# MCU.net
KiCad netlist of a schematic drawn in Altium Designer
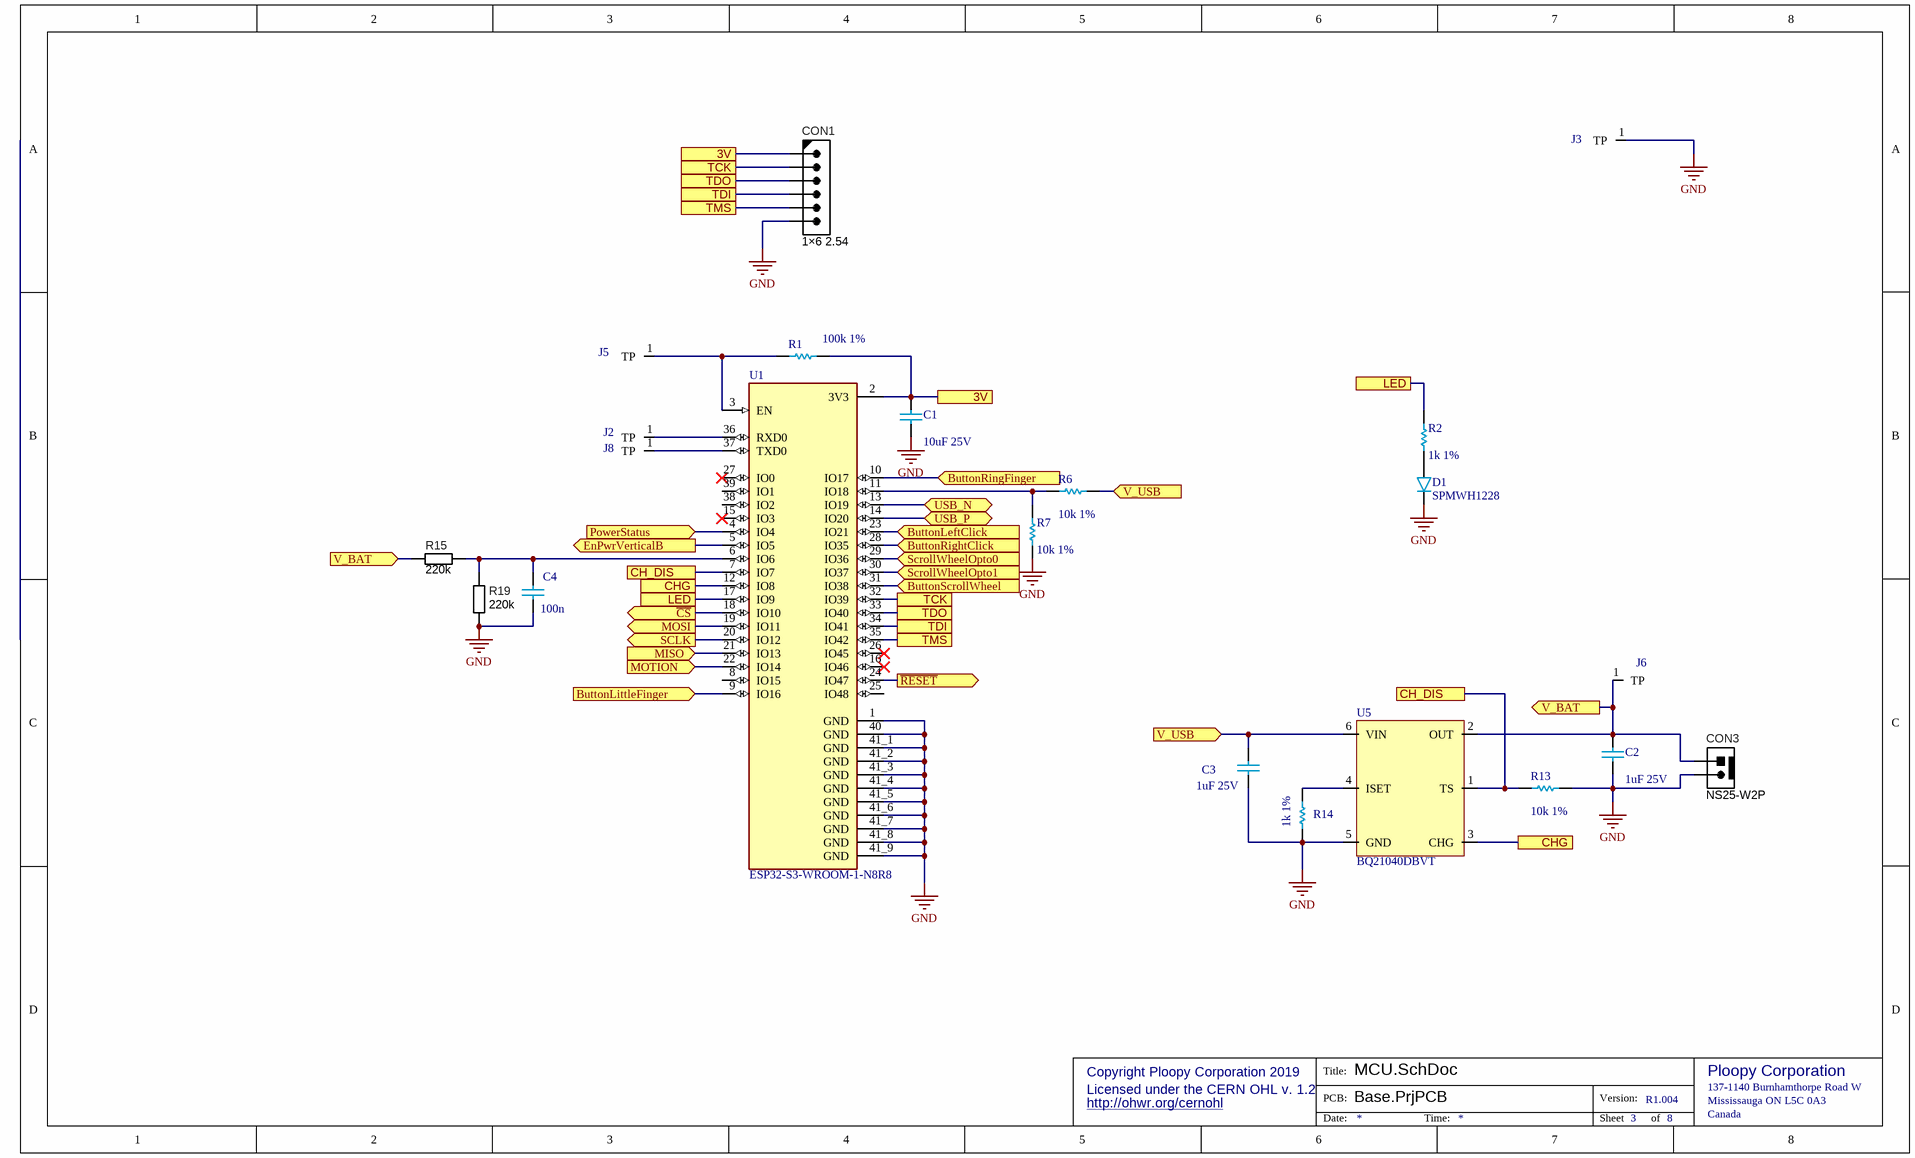
[diagram p0: MCU.SchDoc]

(export (version "E")
  (design (tool "Eeschema 10.0.6"))
  (components
    (comp (ref "C1")
      (value "10uF 25V")
      (footprint "C0603")
      (description "0805, X5R or better")
      (fields (field (name "Comment") "0805"))
      (libsource (lib "Chip_Passives") (part "Cap 10uF 25V"))
    )
    (comp (ref "C2")
      (value "1uF 25V")
      (footprint "C0603")
      (description "0805, X5R or better")
      (fields (field (name "Comment") "0805"))
      (libsource (lib "Chip_Passives") (part "Cap 1uF 25V"))
    )
    (comp (ref "C3")
      (value "1uF 25V")
      (footprint "C0603")
      (description "0805, X5R or better")
      (fields (field (name "Comment") "0805"))
      (libsource (lib "Chip_Passives") (part "Cap 1uF 25V"))
    )
    (comp (ref "C4")
      (value "100n")
      (footprint "C0603")
      (description "0805, X5R or better")
      (fields (field (name "Comment") "0805"))
      (libsource (lib "Chip_Passives") (part "Cap 1uF 25V"))
    )
    (comp (ref "CON1")
      (value "1×6 2.54")
      (footprint "THT_CON:PH2.54_1X6")
      (description "1x3 standart 100mil pinheader")
      (libsource (lib "Connectors") (part "PH2.54_1X6"))
    )
    (comp (ref "CON3")
      (value "NS25-W2P")
      (footprint "THT_CON:MOLEST_L2.54_2W")
      (description "Molex-like 2.54mm connector with lock")
      (libsource (lib "Connectors") (part "MOLEST_L2.54_2W"))
    )
    (comp (ref "D1")
      (value "SPMWH1228")
      (footprint "SPMWH1228")
      (description "3V/0.5W white LED, 2.8mm x 3.5mm")
      (libsource (lib "LEDs") (part "SPMWH1228"))
    )
    (comp (ref "J2")
      (value "TestPoint")
      (footprint "TestPoint")
      (libsource (lib "Schlib1") (part "TestPoint"))
    )
    (comp (ref "J3")
      (value "TestPoint")
      (footprint "TestPoint")
      (libsource (lib "Schlib1") (part "TestPoint"))
    )
    (comp (ref "J5")
      (value "TestPoint")
      (footprint "TestPoint")
      (libsource (lib "Schlib1") (part "TestPoint"))
    )
    (comp (ref "J6")
      (value "TestPoint")
      (footprint "TestPoint")
      (libsource (lib "Schlib1") (part "TestPoint"))
    )
    (comp (ref "J8")
      (value "TestPoint")
      (footprint "TestPoint")
      (libsource (lib "Schlib1") (part "TestPoint"))
    )
    (comp (ref "R1")
      (value "100k 1%")
      (footprint "R0603")
      (description "Chip resistor")
      (fields (field (name "Comment") "0805"))
      (libsource (lib "Chip_Passives") (part "Res 100k 1% 0805"))
    )
    (comp (ref "R2")
      (value "1k 1%")
      (footprint "R0603")
      (description "Chip resistor, 1/8W 100PPM")
      (fields (field (name "Comment") "0805"))
      (libsource (lib "Chip_Passives") (part "Res 1k 1% 0805"))
    )
    (comp (ref "R6")
      (value "10k 1%")
      (footprint "R0603")
      (description "Chip resistor")
      (fields (field (name "Comment") "0805"))
      (libsource (lib "Chip_Passives") (part "Res 10k 1% 0805"))
    )
    (comp (ref "R7")
      (value "10k 1%")
      (footprint "R0603")
      (description "Chip resistor")
      (fields (field (name "Comment") "0805"))
      (libsource (lib "Chip_Passives") (part "Res 10k 1% 0805"))
    )
    (comp (ref "R13")
      (value "10k 1%")
      (footprint "R0603")
      (description "Chip resistor")
      (fields (field (name "Comment") "0805"))
      (libsource (lib "Chip_Passives") (part "Res 10k 1% 0805"))
    )
    (comp (ref "R14")
      (value "1k 1%")
      (footprint "R0603")
      (description "Chip resistor, 1/8W 100PPM")
      (fields (field (name "Comment") "0805"))
      (libsource (lib "Chip_Passives") (part "Res 1k 1% 0805"))
    )
    (comp (ref "R15")
      (value "220k")
      (footprint "SMD_PASSIVES:R0603")
      (description "Generic 0603 resistor footprint")
      (libsource (lib "") (part "R0603_1"))
    )
    (comp (ref "R19")
      (value "220k")
      (footprint "SMD_PASSIVES:R0603")
      (description "Generic 0603 resistor footprint")
      (libsource (lib "Passives") (part "R0603"))
    )
    (comp (ref "U1")
      (value "ESP32-S3-WROOM-1-N8R8")
      (footprint "XCVR_ESP32S3WROOM1N8R8")
      (description "Bluetooth, WiFi 802.11b/g/n, Bluetooth v5.0 Transceiver Module 2.4GHz PCB Trace Surface Mount")
      (fields (field (name "MF") "Espressif Systems"))
      (libsource (lib "ESP32-S3-WROOM-1-N8R8") (part "ESP32-S3-WROOM-1-N8R8"))
    )
    (comp (ref "U5")
      (value "BQ21040DBVT")
      (footprint "PESD3V3S4UD - SOT95P275X110-6N")
      (libsource (lib "Schlib1") (part "BQ21040DBVT"))
    )
  )
  (nets
    (net (code "1") (name "/3V") (class "Default")
      (node (ref "C1") (pin "2") (pinfunction "2_2") (pintype "passive"))
      (node (ref "CON1") (pin "1") (pinfunction "1_1") (pintype "passive"))
      (node (ref "R1") (pin "2") (pinfunction "2_2") (pintype "passive"))
      (node (ref "U1") (pin "2") (pinfunction "3V3_2") (pintype "power_in"))
    )
    (net (code "2") (name "/ButtonLeftClick") (class "Default")
      (node (ref "U1") (pin "23") (pinfunction "IO21_23") (pintype "bidirectional"))
    )
    (net (code "3") (name "/ButtonLittleFinger") (class "Default")
      (node (ref "U1") (pin "9") (pinfunction "IO16_9") (pintype "bidirectional"))
    )
    (net (code "4") (name "/ButtonRightClick") (class "Default")
      (node (ref "U1") (pin "28") (pinfunction "IO35_28") (pintype "bidirectional"))
    )
    (net (code "5") (name "/ButtonRingFinger") (class "Default")
      (node (ref "U1") (pin "10") (pinfunction "IO17_10") (pintype "bidirectional"))
    )
    (net (code "6") (name "/ButtonScrollWheel") (class "Default")
      (node (ref "U1") (pin "31") (pinfunction "IO38_31") (pintype "bidirectional"))
    )
    (net (code "7") (name "/CHG") (class "Default")
      (node (ref "U1") (pin "12") (pinfunction "IO8_12") (pintype "bidirectional"))
      (node (ref "U5") (pin "3") (pinfunction "CHG_3") (pintype "passive"))
    )
    (net (code "8") (name "/CH_DIS") (class "Default")
      (node (ref "R13") (pin "2") (pinfunction "2_2") (pintype "passive"))
      (node (ref "U1") (pin "7") (pinfunction "IO7_7") (pintype "bidirectional"))
      (node (ref "U5") (pin "1") (pinfunction "TS_1") (pintype "passive"))
    )
    (net (code "9") (name "/EnPwrVerticalB") (class "Default")
      (node (ref "U1") (pin "5") (pinfunction "IO5_5") (pintype "bidirectional"))
    )
    (net (code "10") (name "/LED") (class "Default")
      (node (ref "R2") (pin "2") (pinfunction "2_2") (pintype "passive"))
      (node (ref "U1") (pin "17") (pinfunction "IO9_17") (pintype "bidirectional"))
    )
    (net (code "11") (name "/MISO") (class "Default")
      (node (ref "U1") (pin "21") (pinfunction "IO13_21") (pintype "bidirectional"))
    )
    (net (code "12") (name "/MOSI") (class "Default")
      (node (ref "U1") (pin "19") (pinfunction "IO11_19") (pintype "bidirectional"))
    )
    (net (code "13") (name "/MOTION") (class "Default")
      (node (ref "U1") (pin "22") (pinfunction "IO14_22") (pintype "bidirectional"))
    )
    (net (code "14") (name "/PowerStatus") (class "Default")
      (node (ref "U1") (pin "4") (pinfunction "IO4_4") (pintype "bidirectional"))
    )
    (net (code "15") (name "/SCLK") (class "Default")
      (node (ref "U1") (pin "20") (pinfunction "IO12_20") (pintype "bidirectional"))
    )
    (net (code "16") (name "/ScrollWheelOpto0") (class "Default")
      (node (ref "U1") (pin "29") (pinfunction "IO36_29") (pintype "bidirectional"))
    )
    (net (code "17") (name "/ScrollWheelOpto1") (class "Default")
      (node (ref "U1") (pin "30") (pinfunction "IO37_30") (pintype "bidirectional"))
    )
    (net (code "18") (name "/TCK") (class "Default")
      (node (ref "CON1") (pin "2") (pinfunction "2_2") (pintype "passive"))
      (node (ref "U1") (pin "32") (pinfunction "IO39_32") (pintype "bidirectional"))
    )
    (net (code "19") (name "/TDI") (class "Default")
      (node (ref "CON1") (pin "4") (pinfunction "4_4") (pintype "passive"))
      (node (ref "U1") (pin "34") (pinfunction "IO41_34") (pintype "bidirectional"))
    )
    (net (code "20") (name "/TDO") (class "Default")
      (node (ref "CON1") (pin "3") (pinfunction "3_3") (pintype "passive"))
      (node (ref "U1") (pin "33") (pinfunction "IO40_33") (pintype "bidirectional"))
    )
    (net (code "21") (name "/TMS") (class "Default")
      (node (ref "CON1") (pin "5") (pinfunction "5_5") (pintype "passive"))
      (node (ref "U1") (pin "35") (pinfunction "IO42_35") (pintype "bidirectional"))
    )
    (net (code "22") (name "/USB_N") (class "Default")
      (node (ref "U1") (pin "13") (pinfunction "IO19_13") (pintype "bidirectional"))
    )
    (net (code "23") (name "/USB_P") (class "Default")
      (node (ref "U1") (pin "14") (pinfunction "IO20_14") (pintype "bidirectional"))
    )
    (net (code "24") (name "/V_BAT") (class "Default")
      (node (ref "C2") (pin "2") (pinfunction "2_2") (pintype "passive"))
      (node (ref "CON3") (pin "1") (pinfunction "1_1") (pintype "passive"))
      (node (ref "J6") (pin "1") (pinfunction "TP_1") (pintype "passive"))
      (node (ref "R15") (pin "1") (pinfunction "1_1") (pintype "passive"))
      (node (ref "U5") (pin "2") (pinfunction "OUT_2") (pintype "passive"))
    )
    (net (code "25") (name "/V_USB") (class "Default")
      (node (ref "C3") (pin "2") (pinfunction "2_2") (pintype "passive"))
      (node (ref "R6") (pin "2") (pinfunction "2_2") (pintype "passive"))
      (node (ref "U5") (pin "6") (pinfunction "VIN_6") (pintype "passive"))
    )
    (net (code "26") (name "/~{CS}") (class "Default")
      (node (ref "U1") (pin "18") (pinfunction "IO10_18") (pintype "bidirectional"))
    )
    (net (code "27") (name "/~{RESET}") (class "Default")
      (node (ref "U1") (pin "24") (pinfunction "IO47_24") (pintype "bidirectional"))
    )
    (net (code "28") (name "GND") (class "Default")
      (node (ref "C1") (pin "1") (pinfunction "1_1") (pintype "passive"))
      (node (ref "C2") (pin "1") (pinfunction "1_1") (pintype "passive"))
      (node (ref "C3") (pin "1") (pinfunction "1_1") (pintype "passive"))
      (node (ref "C4") (pin "1") (pinfunction "1_1") (pintype "passive"))
      (node (ref "CON1") (pin "6") (pinfunction "6_6") (pintype "passive"))
      (node (ref "CON3") (pin "2") (pinfunction "2_2") (pintype "passive"))
      (node (ref "D1") (pin "2") (pinfunction "C_2") (pintype "passive"))
      (node (ref "J3") (pin "1") (pinfunction "TP_1") (pintype "passive"))
      (node (ref "R13") (pin "1") (pinfunction "1_1") (pintype "passive"))
      (node (ref "R14") (pin "1") (pinfunction "1_1") (pintype "passive"))
      (node (ref "R19") (pin "1") (pinfunction "1_1") (pintype "passive"))
      (node (ref "R7") (pin "1") (pinfunction "1_1") (pintype "passive"))
      (node (ref "U1") (pin "1") (pinfunction "GND_1") (pintype "power_in"))
      (node (ref "U1") (pin "40") (pinfunction "GND_40") (pintype "power_in"))
      (node (ref "U1") (pin "41_1") (pinfunction "GND_41_1") (pintype "power_in"))
      (node (ref "U1") (pin "41_2") (pinfunction "GND_41_2") (pintype "power_in"))
      (node (ref "U1") (pin "41_3") (pinfunction "GND_41_3") (pintype "power_in"))
      (node (ref "U1") (pin "41_4") (pinfunction "GND_41_4") (pintype "power_in"))
      (node (ref "U1") (pin "41_5") (pinfunction "GND_41_5") (pintype "power_in"))
      (node (ref "U1") (pin "41_6") (pinfunction "GND_41_6") (pintype "power_in"))
      (node (ref "U1") (pin "41_7") (pinfunction "GND_41_7") (pintype "power_in"))
      (node (ref "U1") (pin "41_8") (pinfunction "GND_41_8") (pintype "power_in"))
      (node (ref "U1") (pin "41_9") (pinfunction "GND_41_9") (pintype "power_in"))
      (node (ref "U5") (pin "5") (pinfunction "GND_5") (pintype "passive"))
    )
    (net (code "29") (name "Net-(D1-A)") (class "Default")
      (node (ref "D1") (pin "1") (pinfunction "A_1") (pintype "passive"))
      (node (ref "R2") (pin "1") (pinfunction "1_1") (pintype "passive"))
    )
    (net (code "30") (name "Net-(J2-TP)") (class "Default")
      (node (ref "J2") (pin "1") (pinfunction "TP_1") (pintype "passive"))
      (node (ref "U1") (pin "36") (pinfunction "RXD0_36") (pintype "bidirectional"))
    )
    (net (code "31") (name "Net-(J5-TP)") (class "Default")
      (node (ref "J5") (pin "1") (pinfunction "TP_1") (pintype "passive"))
      (node (ref "R1") (pin "1") (pinfunction "1_1") (pintype "passive"))
      (node (ref "U1") (pin "3") (pinfunction "EN_3") (pintype "input"))
    )
    (net (code "32") (name "Net-(J8-TP)") (class "Default")
      (node (ref "J8") (pin "1") (pinfunction "TP_1") (pintype "passive"))
      (node (ref "U1") (pin "37") (pinfunction "TXD0_37") (pintype "bidirectional"))
    )
    (net (code "33") (name "Net-(U1-IO6)") (class "Default")
      (node (ref "C4") (pin "2") (pinfunction "2_2") (pintype "passive"))
      (node (ref "R15") (pin "2") (pinfunction "2_2") (pintype "passive"))
      (node (ref "R19") (pin "2") (pinfunction "2_2") (pintype "passive"))
      (node (ref "U1") (pin "6") (pinfunction "IO6_6") (pintype "bidirectional"))
    )
    (net (code "34") (name "Net-(U1-IO18)") (class "Default")
      (node (ref "R6") (pin "1") (pinfunction "1_1") (pintype "passive"))
      (node (ref "R7") (pin "2") (pinfunction "2_2") (pintype "passive"))
      (node (ref "U1") (pin "11") (pinfunction "IO18_11") (pintype "bidirectional"))
    )
    (net (code "35") (name "Net-(U5-ISET)") (class "Default")
      (node (ref "R14") (pin "2") (pinfunction "2_2") (pintype "passive"))
      (node (ref "U5") (pin "4") (pinfunction "ISET_4") (pintype "passive"))
    )
    (net (code "36") (name "unconnected-(U1-IO0-Pad27)") (class "Default")
      (node (ref "U1") (pin "27") (pinfunction "IO0_27") (pintype "bidirectional+no_connect"))
    )
    (net (code "37") (name "unconnected-(U1-IO1-Pad39)") (class "Default")
      (node (ref "U1") (pin "39") (pinfunction "IO1_39") (pintype "bidirectional"))
    )
    (net (code "38") (name "unconnected-(U1-IO2-Pad38)") (class "Default")
      (node (ref "U1") (pin "38") (pinfunction "IO2_38") (pintype "bidirectional"))
    )
    (net (code "39") (name "unconnected-(U1-IO3-Pad15)") (class "Default")
      (node (ref "U1") (pin "15") (pinfunction "IO3_15") (pintype "bidirectional+no_connect"))
    )
    (net (code "40") (name "unconnected-(U1-IO15-Pad8)") (class "Default")
      (node (ref "U1") (pin "8") (pinfunction "IO15_8") (pintype "bidirectional"))
    )
    (net (code "41") (name "unconnected-(U1-IO45-Pad26)") (class "Default")
      (node (ref "U1") (pin "26") (pinfunction "IO45_26") (pintype "bidirectional+no_connect"))
    )
    (net (code "42") (name "unconnected-(U1-IO46-Pad16)") (class "Default")
      (node (ref "U1") (pin "16") (pinfunction "IO46_16") (pintype "bidirectional+no_connect"))
    )
    (net (code "43") (name "unconnected-(U1-IO48-Pad25)") (class "Default")
      (node (ref "U1") (pin "25") (pinfunction "IO48_25") (pintype "bidirectional"))
    )
  )
)
